# SCH_WS2812B-IR-Controller_2024-06-23.net
KiCad netlist of a schematic drawn in EasyEDA
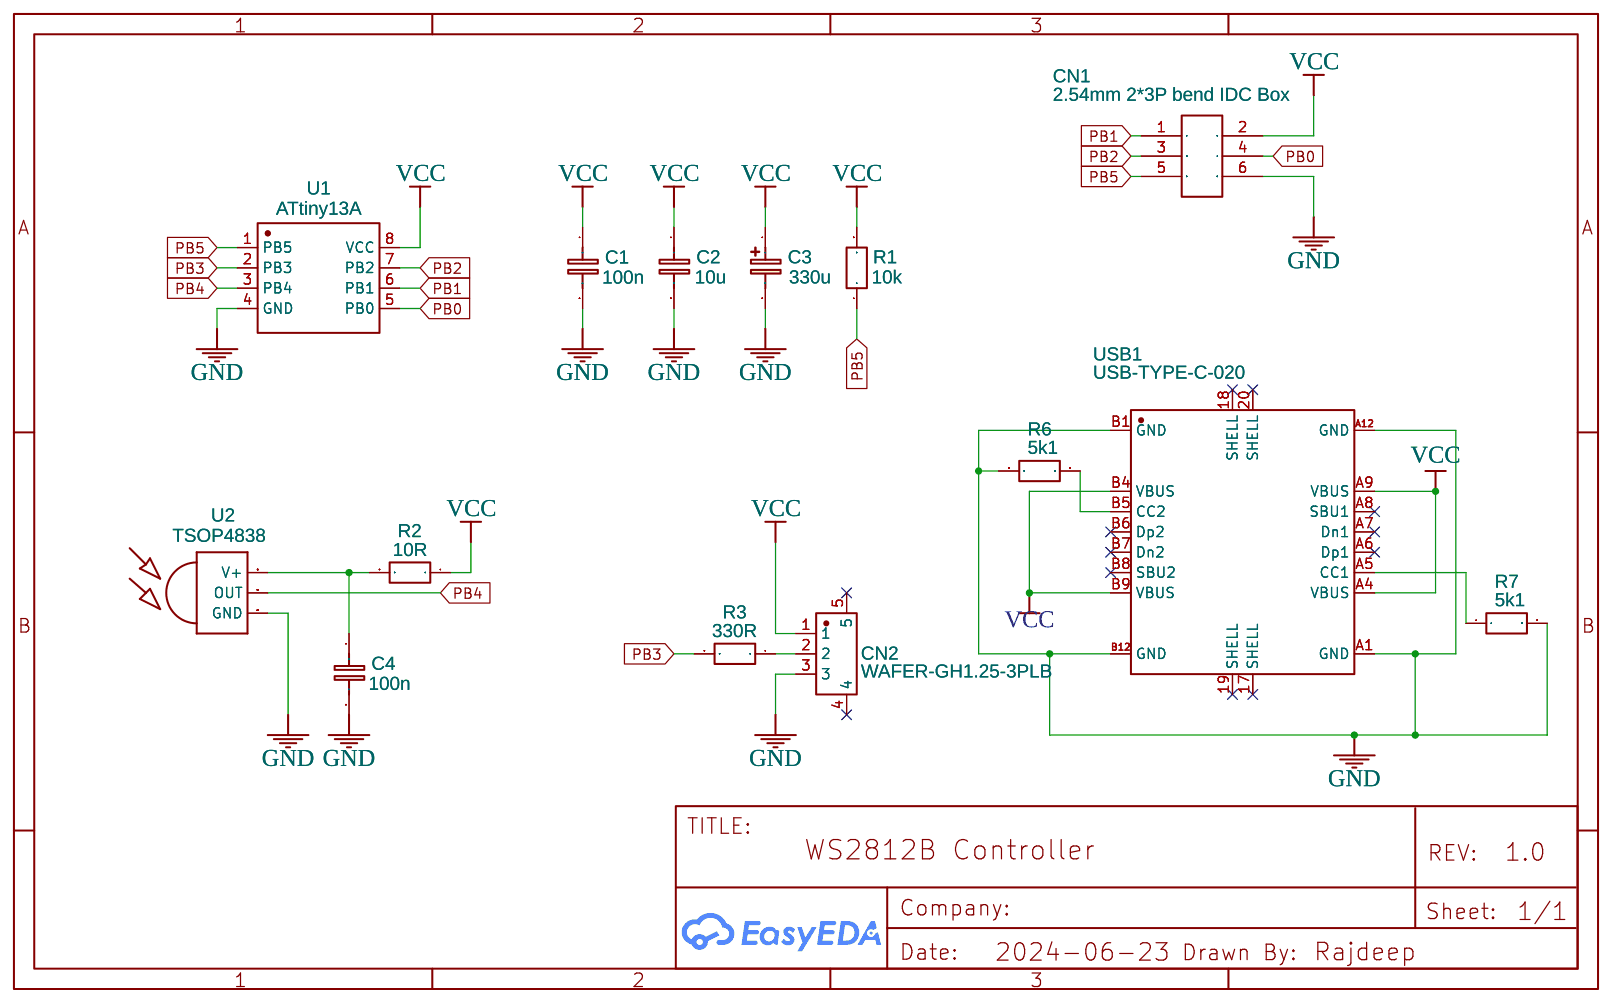
[diagram p0: schematic sheet]

(export (version "E")
  (design (tool "Eeschema 10.0.6"))
  (components
    (comp (ref "C1")
      (value "100n")
      (fields (field (name "Manufacturer Part") "CC0603KRX7R9BB104") (field (name "Manufacturer") "YAGEO"))
      (libsource (lib "") (part "Cap_0603_EU"))
    )
    (comp (ref "C2")
      (value "10u")
      (fields (field (name "Manufacturer Part") "CL10A106MA8NRNC") (field (name "Manufacturer") "SAMSUNG"))
      (libsource (lib "") (part "Cap_0603_EU"))
    )
    (comp (ref "C3")
      (value "330u")
      (fields (field (name "Manufacturer Part") "TAJD337M010RNJ") (field (name "Manufacturer") "AVX"))
      (libsource (lib "") (part "Cap_Tantalum(SMD)_D-7343_EU"))
    )
    (comp (ref "C4")
      (value "100n")
      (fields (field (name "Manufacturer Part") "CC0603KRX7R9BB104") (field (name "Manufacturer") "YAGEO"))
      (libsource (lib "") (part "Cap_0603_EU"))
    )
    (comp (ref "CN1")
      (value "2.54mm 2*3P bend IDC Box")
      (fields (field (name "Manufacturer Part") "2.54-2*3P弯简牛") (field (name "Manufacturer") "BOOMELE(博穆精密)"))
      (libsource (lib "") (part "2.54mm 2*3P bend IDC Box"))
    )
    (comp (ref "CN2")
      (value "WAFER-GH1.25-3PLB")
      (fields (field (name "Manufacturer") "XUNPU(讯普)"))
      (libsource (lib "") (part "WAFER-GH1.25-3PLB"))
    )
    (comp (ref "R1")
      (value "10k")
      (fields (field (name "Manufacturer Part") "0603WAF1002T5E") (field (name "Manufacturer") "UniOhm"))
      (libsource (lib "") (part "Res_0603(1/10W)_EU_2"))
    )
    (comp (ref "R2")
      (value "10R")
      (fields (field (name "Manufacturer Part") "0603WAF100JT5E") (field (name "Manufacturer") "UniOhm"))
      (libsource (lib "") (part "Res_0603(1/10W)_EU"))
    )
    (comp (ref "R3")
      (value "330R")
      (fields (field (name "Manufacturer Part") "0603WAF3300T5E") (field (name "Manufacturer") "UniOhm"))
      (libsource (lib "") (part "Res_0603(1/10W)_EU"))
    )
    (comp (ref "R6")
      (value "5k1")
      (fields (field (name "Manufacturer Part") "0603WAF5101T5E") (field (name "Manufacturer") "UniOhm"))
      (libsource (lib "") (part "Res_0603(1/10W)_EU_1"))
    )
    (comp (ref "R7")
      (value "5k1")
      (fields (field (name "Manufacturer Part") "0603WAF5101T5E") (field (name "Manufacturer") "UniOhm"))
      (libsource (lib "") (part "Res_0603(1/10W)_EU_1"))
    )
    (comp (ref "U1")
      (value "ATtiny13A")
      (fields (field (name "Manufacturer Part") "ATTINY13A-SSU") (field (name "Manufacturer") "MICROCHIP"))
      (libsource (lib "") (part "Unknown_150_-350"))
    )
    (comp (ref "U2")
      (value "TSOP4838")
      (fields (field (name "Manufacturer") "VISHAY"))
      (libsource (lib "") (part "TSOP4856"))
    )
    (comp (ref "USB1")
      (value "USB-TYPE-C-020")
      (fields (field (name "Manufacturer") "DEALON(德艺隆)"))
      (libsource (lib "") (part "USB-TYPE-C-020"))
    )
  )
  (nets
    (net (code "1") (name "GND") (class "Default")
      (node (ref "C1") (pin "2") (pinfunction "2_2") (pintype "unspecified"))
      (node (ref "C2") (pin "2") (pinfunction "2_2") (pintype "unspecified"))
      (node (ref "C3") (pin "2") (pinfunction "2_2") (pintype "unspecified"))
      (node (ref "C4") (pin "2") (pinfunction "2_2") (pintype "unspecified"))
      (node (ref "CN1") (pin "6") (pinfunction "6_6") (pintype "unspecified"))
      (node (ref "CN2") (pin "3") (pinfunction "3_3") (pintype "unspecified"))
      (node (ref "R6") (pin "1") (pinfunction "1_1") (pintype "unspecified"))
      (node (ref "R7") (pin "2") (pinfunction "2_2") (pintype "unspecified"))
      (node (ref "U1") (pin "4") (pinfunction "GND_4") (pintype "unspecified"))
      (node (ref "U2") (pin "GND") (pinfunction "GND_GND") (pintype "unspecified"))
      (node (ref "USB1") (pin "A1") (pinfunction "GND_A1") (pintype "unspecified"))
      (node (ref "USB1") (pin "A12") (pinfunction "GND_A12") (pintype "unspecified"))
      (node (ref "USB1") (pin "B1") (pinfunction "GND_B1") (pintype "unspecified"))
      (node (ref "USB1") (pin "B12") (pinfunction "GND_B12") (pintype "unspecified"))
    )
    (net (code "2") (name "Net-(CN2-Pad2)") (class "Default")
      (node (ref "CN2") (pin "2") (pinfunction "2_2") (pintype "unspecified"))
      (node (ref "R3") (pin "1") (pinfunction "1_1") (pintype "unspecified"))
    )
    (net (code "3") (name "Net-(U2-V+)") (class "Default")
      (node (ref "C4") (pin "1") (pinfunction "1_1") (pintype "unspecified"))
      (node (ref "R2") (pin "2") (pinfunction "2_2") (pintype "unspecified"))
      (node (ref "U2") (pin "VCC") (pinfunction "V+_VCC") (pintype "unspecified"))
    )
    (net (code "4") (name "Net-(USB1-CC1)") (class "Default")
      (node (ref "R7") (pin "1") (pinfunction "1_1") (pintype "unspecified"))
      (node (ref "USB1") (pin "A5") (pinfunction "CC1_A5") (pintype "unspecified"))
    )
    (net (code "5") (name "Net-(USB1-CC2)") (class "Default")
      (node (ref "R6") (pin "2") (pinfunction "2_2") (pintype "unspecified"))
      (node (ref "USB1") (pin "B5") (pinfunction "CC2_B5") (pintype "unspecified"))
    )
    (net (code "6") (name "PB0") (class "Default")
      (node (ref "CN1") (pin "4") (pinfunction "4_4") (pintype "unspecified"))
      (node (ref "U1") (pin "5") (pinfunction "PB0_5") (pintype "unspecified"))
    )
    (net (code "7") (name "PB1") (class "Default")
      (node (ref "CN1") (pin "1") (pinfunction "1_1") (pintype "unspecified"))
      (node (ref "U1") (pin "6") (pinfunction "PB1_6") (pintype "unspecified"))
    )
    (net (code "8") (name "PB2") (class "Default")
      (node (ref "CN1") (pin "3") (pinfunction "3_3") (pintype "unspecified"))
      (node (ref "U1") (pin "7") (pinfunction "PB2_7") (pintype "unspecified"))
    )
    (net (code "9") (name "PB3") (class "Default")
      (node (ref "R3") (pin "2") (pinfunction "2_2") (pintype "unspecified"))
      (node (ref "U1") (pin "2") (pinfunction "PB3_2") (pintype "unspecified"))
    )
    (net (code "10") (name "PB4") (class "Default")
      (node (ref "U1") (pin "3") (pinfunction "PB4_3") (pintype "unspecified"))
      (node (ref "U2") (pin "OUT") (pinfunction "OUT_OUT") (pintype "unspecified"))
    )
    (net (code "11") (name "PB5") (class "Default")
      (node (ref "CN1") (pin "5") (pinfunction "5_5") (pintype "unspecified"))
      (node (ref "R1") (pin "1") (pinfunction "1_1") (pintype "unspecified"))
      (node (ref "U1") (pin "1") (pinfunction "PB5_1") (pintype "unspecified"))
    )
    (net (code "12") (name "VCC") (class "Default")
      (node (ref "C1") (pin "1") (pinfunction "1_1") (pintype "unspecified"))
      (node (ref "C2") (pin "1") (pinfunction "1_1") (pintype "unspecified"))
      (node (ref "C3") (pin "1") (pinfunction "1_1") (pintype "unspecified"))
      (node (ref "CN1") (pin "2") (pinfunction "2_2") (pintype "unspecified"))
      (node (ref "CN2") (pin "1") (pinfunction "1_1") (pintype "unspecified"))
      (node (ref "R1") (pin "2") (pinfunction "2_2") (pintype "unspecified"))
      (node (ref "R2") (pin "1") (pinfunction "1_1") (pintype "unspecified"))
      (node (ref "U1") (pin "8") (pinfunction "VCC_8") (pintype "unspecified"))
      (node (ref "USB1") (pin "A4") (pinfunction "VBUS_A4") (pintype "unspecified"))
      (node (ref "USB1") (pin "A9") (pinfunction "VBUS_A9") (pintype "unspecified"))
      (node (ref "USB1") (pin "B4") (pinfunction "VBUS_B4") (pintype "unspecified"))
      (node (ref "USB1") (pin "B9") (pinfunction "VBUS_B9") (pintype "unspecified"))
    )
    (net (code "13") (name "unconnected-(CN2-Pad4)") (class "Default")
      (node (ref "CN2") (pin "4") (pinfunction "4_4") (pintype "unspecified+no_connect"))
    )
    (net (code "14") (name "unconnected-(CN2-Pad5)") (class "Default")
      (node (ref "CN2") (pin "5") (pinfunction "5_5") (pintype "unspecified+no_connect"))
    )
    (net (code "15") (name "unconnected-(USB1-Dn1-PadA7)") (class "Default")
      (node (ref "USB1") (pin "A7") (pinfunction "Dn1_A7") (pintype "unspecified+no_connect"))
    )
    (net (code "16") (name "unconnected-(USB1-Dn2-PadB7)") (class "Default")
      (node (ref "USB1") (pin "B7") (pinfunction "Dn2_B7") (pintype "unspecified+no_connect"))
    )
    (net (code "17") (name "unconnected-(USB1-Dp1-PadA6)") (class "Default")
      (node (ref "USB1") (pin "A6") (pinfunction "Dp1_A6") (pintype "unspecified+no_connect"))
    )
    (net (code "18") (name "unconnected-(USB1-Dp2-PadB6)") (class "Default")
      (node (ref "USB1") (pin "B6") (pinfunction "Dp2_B6") (pintype "unspecified+no_connect"))
    )
    (net (code "19") (name "unconnected-(USB1-SBU1-PadA8)") (class "Default")
      (node (ref "USB1") (pin "A8") (pinfunction "SBU1_A8") (pintype "unspecified+no_connect"))
    )
    (net (code "20") (name "unconnected-(USB1-SBU2-PadB8)") (class "Default")
      (node (ref "USB1") (pin "B8") (pinfunction "SBU2_B8") (pintype "unspecified+no_connect"))
    )
    (net (code "21") (name "unconnected-(USB1-SHELL-Pad17)") (class "Default")
      (node (ref "USB1") (pin "17") (pinfunction "SHELL_17") (pintype "unspecified+no_connect"))
    )
    (net (code "22") (name "unconnected-(USB1-SHELL-Pad18)") (class "Default")
      (node (ref "USB1") (pin "18") (pinfunction "SHELL_18") (pintype "unspecified+no_connect"))
    )
    (net (code "23") (name "unconnected-(USB1-SHELL-Pad19)") (class "Default")
      (node (ref "USB1") (pin "19") (pinfunction "SHELL_19") (pintype "unspecified+no_connect"))
    )
    (net (code "24") (name "unconnected-(USB1-SHELL-Pad20)") (class "Default")
      (node (ref "USB1") (pin "20") (pinfunction "SHELL_20") (pintype "unspecified+no_connect"))
    )
  )
)
